# keyboard.net
KiCad netlist of a schematic drawn in EAGLE
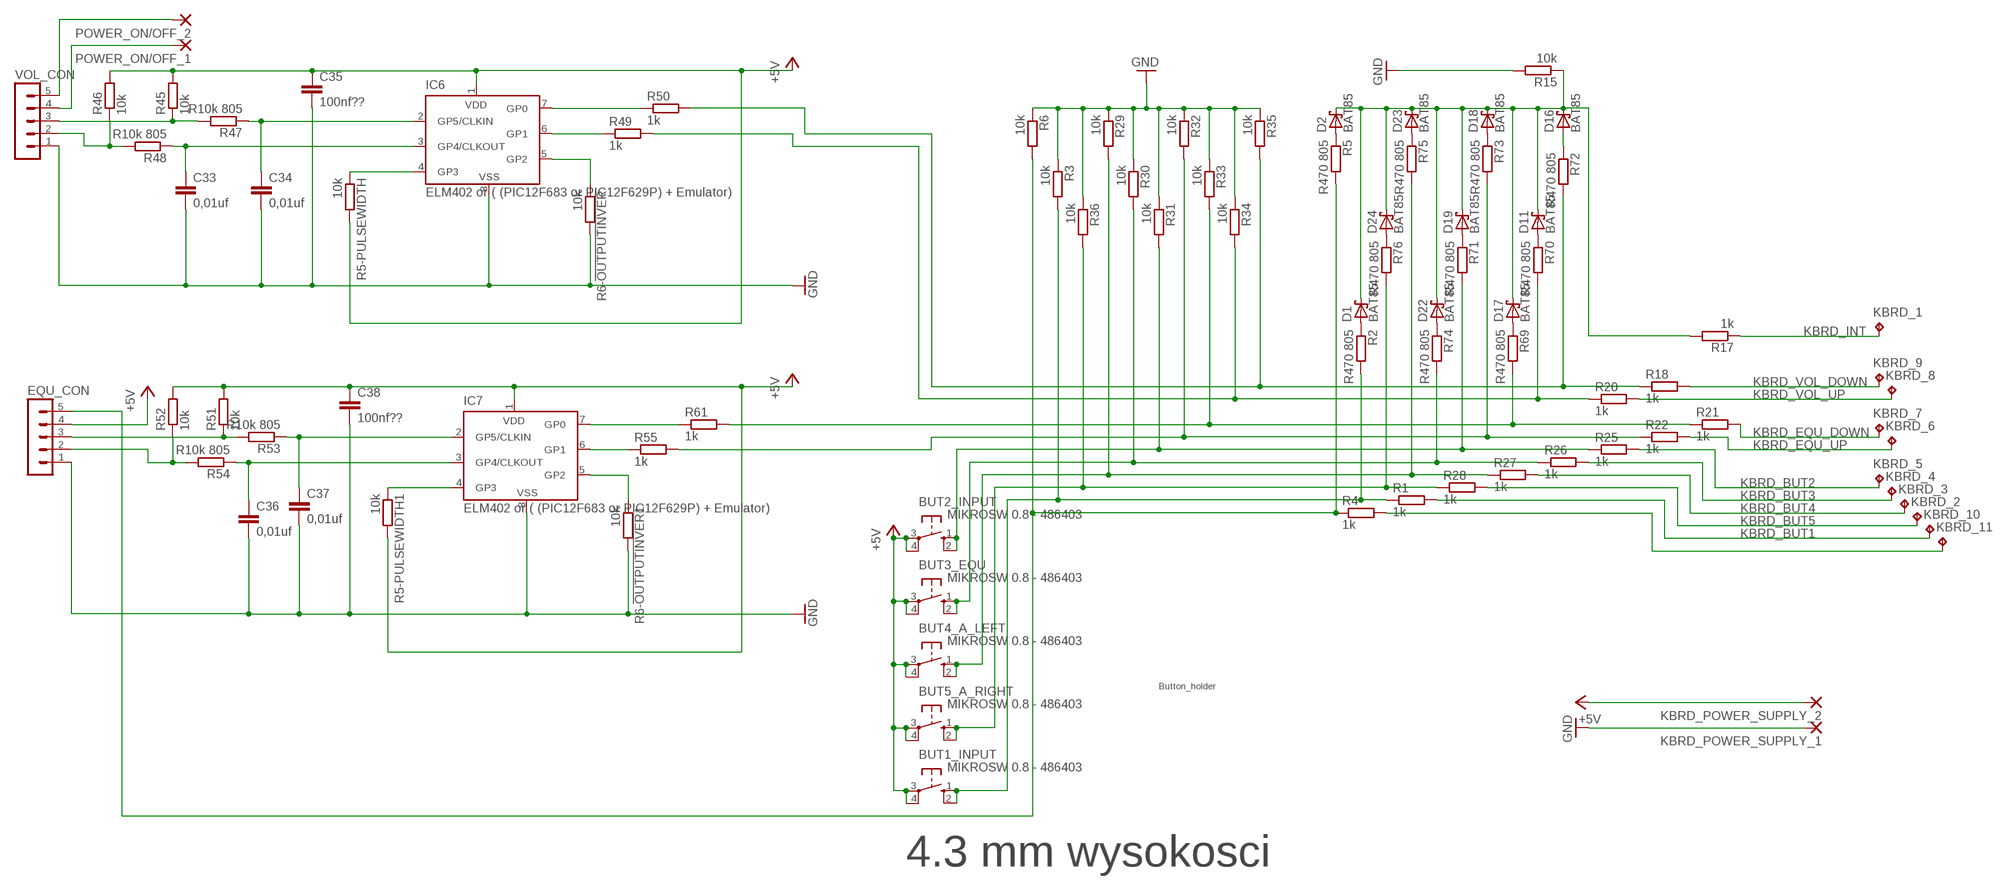
[diagram p0: schematic, sheet 1]

(export (version "E")
  (design (tool "Eeschema 10.0.6"))
  (components
    (comp (ref "BUT1_INPUT")
      (value "MIKROSW 0.8 - 486403")
      (footprint "eagle-import:B3F-10XX")
      (fields
        (field (name "MPN") "B3F-1000")
        (field (name "MF") "OMRON ELECTRONIC COMPONENTS")
        (field (name "MPN_1") "B3F-1000")
        (field (name "OC_FARNELL") "176432")
        (field (name "OC_NEWARK") "36M3542")
      )
      (libsource (lib "eagle-import") (part "10-XX"))
    )
    (comp (ref "BUT2_INPUT")
      (value "MIKROSW 0.8 - 486403")
      (footprint "eagle-import:B3F-10XX")
      (fields
        (field (name "MPN") "B3F-1000")
        (field (name "MF") "OMRON ELECTRONIC COMPONENTS")
        (field (name "MPN_1") "B3F-1000")
        (field (name "OC_FARNELL") "176432")
      )
      (libsource (lib "eagle-import") (part "10-XX"))
    )
    (comp (ref "BUT3_EQU")
      (value "MIKROSW 0.8 - 486403")
      (footprint "eagle-import:B3F-10XX")
      (fields
        (field (name "MPN") "B3F-1000")
        (field (name "MF") "OMRON ELECTRONIC COMPONENTS")
        (field (name "MPN_1") "B3F-1000")
        (field (name "OC_FARNELL") "176432")
      )
      (libsource (lib "eagle-import") (part "10-XX"))
    )
    (comp (ref "BUT4_A_LEFT")
      (value "MIKROSW 0.8 - 486403")
      (footprint "eagle-import:B3F-10XX")
      (fields
        (field (name "MPN") "B3F-1000")
        (field (name "MF") "OMRON ELECTRONIC COMPONENTS")
        (field (name "MPN_1") "B3F-1000")
        (field (name "OC_FARNELL") "176432")
      )
      (libsource (lib "eagle-import") (part "10-XX"))
    )
    (comp (ref "BUT5_A_RIGHT")
      (value "MIKROSW 0.8 - 486403")
      (footprint "eagle-import:B3F-10XX")
      (fields
        (field (name "MPN") "B3F-1000")
        (field (name "MF") "OMRON ELECTRONIC COMPONENTS")
        (field (name "MPN_1") "B3F-1000")
        (field (name "OC_FARNELL") "176432")
      )
      (libsource (lib "eagle-import") (part "10-XX"))
    )
    (comp (ref "C33")
      (value "0,01uf")
      (footprint "eagle-import:C0805")
      (libsource (lib "eagle-import") (part "C-EUC0805"))
    )
    (comp (ref "C34")
      (value "0,01uf")
      (footprint "eagle-import:C0805")
      (libsource (lib "eagle-import") (part "C-EUC0805"))
    )
    (comp (ref "C35")
      (value "100nf??")
      (footprint "eagle-import:C0805")
      (libsource (lib "eagle-import") (part "C-EUC0805"))
    )
    (comp (ref "C36")
      (value "0,01uf")
      (footprint "eagle-import:C0805")
      (libsource (lib "eagle-import") (part "C-EUC0805"))
    )
    (comp (ref "C37")
      (value "0,01uf")
      (footprint "eagle-import:C0805")
      (libsource (lib "eagle-import") (part "C-EUC0805"))
    )
    (comp (ref "C38")
      (value "100nf??")
      (footprint "eagle-import:C0805")
      (libsource (lib "eagle-import") (part "C-EUC0805"))
    )
    (comp (ref "D1")
      (value "BAT85")
      (footprint "eagle-import:DO34-5")
      (libsource (lib "eagle-import") (part "BAT85DO34-5"))
    )
    (comp (ref "D2")
      (value "BAT85")
      (footprint "eagle-import:DO34-5")
      (libsource (lib "eagle-import") (part "BAT85DO34-5"))
    )
    (comp (ref "D11")
      (value "BAT85")
      (footprint "eagle-import:DO34-5")
      (libsource (lib "eagle-import") (part "BAT85DO34-5"))
    )
    (comp (ref "D16")
      (value "BAT85")
      (footprint "eagle-import:DO34-5")
      (libsource (lib "eagle-import") (part "BAT85DO34-5"))
    )
    (comp (ref "D17")
      (value "BAT85")
      (footprint "eagle-import:DO34-5")
      (libsource (lib "eagle-import") (part "BAT85DO34-5"))
    )
    (comp (ref "D18")
      (value "BAT85")
      (footprint "eagle-import:DO34-5")
      (libsource (lib "eagle-import") (part "BAT85DO34-5"))
    )
    (comp (ref "D19")
      (value "BAT85")
      (footprint "eagle-import:DO34-5")
      (libsource (lib "eagle-import") (part "BAT85DO34-5"))
    )
    (comp (ref "D22")
      (value "BAT85")
      (footprint "eagle-import:DO34-5")
      (libsource (lib "eagle-import") (part "BAT85DO34-5"))
    )
    (comp (ref "D23")
      (value "BAT85")
      (footprint "eagle-import:DO34-5")
      (libsource (lib "eagle-import") (part "BAT85DO34-5"))
    )
    (comp (ref "D24")
      (value "BAT85")
      (footprint "eagle-import:DO34-5")
      (libsource (lib "eagle-import") (part "BAT85DO34-5"))
    )
    (comp (ref "EQU_CON")
      (value "MA05-1")
      (footprint "eagle-import:MA05-1")
      (fields (field (name "OC_FARNELL") "unknown") (field (name "OC_NEWARK") "unknown"))
      (libsource (lib "eagle-import") (part "MA05-1"))
    )
    (comp (ref "IC6")
      (value "ELM402 or ( (PIC12F683 or PIC12F629P) + Emulator)")
      (footprint "eagle-import:DIL8")
      (fields
        (field (name "MF") "MICROCHIP")
        (field (name "MPN") "PIC12F629-I/P")
        (field (name "MF_1") "MICROCHIP")
        (field (name "MPN_1") "PIC12F629-E/P")
        (field (name "OC_FARNELL") "1292253")
      )
      (libsource (lib "eagle-import") (part "PIC12F6P29"))
    )
    (comp (ref "IC7")
      (value "ELM402 or ( (PIC12F683 or PIC12F629P) + Emulator)")
      (footprint "eagle-import:DIL8")
      (fields
        (field (name "MF") "MICROCHIP")
        (field (name "MPN") "PIC12F629-I/P")
        (field (name "MF_1") "MICROCHIP")
        (field (name "MPN_1") "PIC12F629-E/P")
        (field (name "OC_FARNELL") "1292253")
      )
      (libsource (lib "eagle-import") (part "PIC12F6P29"))
    )
    (comp (ref "KBRD_1")
      (value "TPPAD1-13Y")
      (footprint "eagle-import:P1-13Y")
      (libsource (lib "eagle-import") (part "TPPAD1-13Y"))
    )
    (comp (ref "KBRD_2")
      (value "TPPAD1-13Y")
      (footprint "eagle-import:P1-13Y")
      (libsource (lib "eagle-import") (part "TPPAD1-13Y"))
    )
    (comp (ref "KBRD_3")
      (value "TPPAD1-13Y")
      (footprint "eagle-import:P1-13Y")
      (libsource (lib "eagle-import") (part "TPPAD1-13Y"))
    )
    (comp (ref "KBRD_4")
      (value "TPPAD1-13Y")
      (footprint "eagle-import:P1-13Y")
      (libsource (lib "eagle-import") (part "TPPAD1-13Y"))
    )
    (comp (ref "KBRD_5")
      (value "TPPAD1-13Y")
      (footprint "eagle-import:P1-13Y")
      (libsource (lib "eagle-import") (part "TPPAD1-13Y"))
    )
    (comp (ref "KBRD_6")
      (value "TPPAD1-13Y")
      (footprint "eagle-import:P1-13Y")
      (libsource (lib "eagle-import") (part "TPPAD1-13Y"))
    )
    (comp (ref "KBRD_7")
      (value "TPPAD1-13Y")
      (footprint "eagle-import:P1-13Y")
      (libsource (lib "eagle-import") (part "TPPAD1-13Y"))
    )
    (comp (ref "KBRD_8")
      (value "TPPAD1-13Y")
      (footprint "eagle-import:P1-13Y")
      (libsource (lib "eagle-import") (part "TPPAD1-13Y"))
    )
    (comp (ref "KBRD_9")
      (value "TPPAD1-13Y")
      (footprint "eagle-import:P1-13Y")
      (libsource (lib "eagle-import") (part "TPPAD1-13Y"))
    )
    (comp (ref "KBRD_10")
      (value "TPPAD1-13Y")
      (footprint "eagle-import:P1-13Y")
      (libsource (lib "eagle-import") (part "TPPAD1-13Y"))
    )
    (comp (ref "KBRD_11")
      (value "TPPAD1-13Y")
      (footprint "eagle-import:P1-13Y")
      (libsource (lib "eagle-import") (part "TPPAD1-13Y"))
    )
    (comp (ref "KBRD_POWER_SUPPLY_1")
      (value "1,6/0,9")
      (footprint "eagle-import:1,6_0,9")
      (libsource (lib "eagle-import") (part "1,6/0,9"))
    )
    (comp (ref "KBRD_POWER_SUPPLY_2")
      (value "1,6/0,9")
      (footprint "eagle-import:1,6_0,9")
      (libsource (lib "eagle-import") (part "1,6/0,9"))
    )
    (comp (ref "POWER_ON/OFF_1")
      (value "2,15/1,0")
      (footprint "eagle-import:2,15_1,0")
      (libsource (lib "eagle-import") (part "2,15/1,0"))
    )
    (comp (ref "POWER_ON/OFF_2")
      (value "2,15/1,0")
      (footprint "eagle-import:2,15_1,0")
      (libsource (lib "eagle-import") (part "2,15/1,0"))
    )
    (comp (ref "R1")
      (value "1k")
      (footprint "eagle-import:R0805")
      (libsource (lib "eagle-import") (part "R-EU_R0805"))
    )
    (comp (ref "R2")
      (value "R470 805")
      (footprint "eagle-import:R0805")
      (libsource (lib "eagle-import") (part "R-EU_R0805"))
    )
    (comp (ref "R3")
      (value "10k")
      (footprint "eagle-import:R0805")
      (libsource (lib "eagle-import") (part "R-EU_R0805"))
    )
    (comp (ref "R4")
      (value "1k")
      (footprint "eagle-import:R0805")
      (libsource (lib "eagle-import") (part "R-EU_R0805"))
    )
    (comp (ref "R5")
      (value "R470 805")
      (footprint "eagle-import:R0805")
      (libsource (lib "eagle-import") (part "R-EU_R0805"))
    )
    (comp (ref "R5-PULSEWIDTH")
      (value "10k")
      (footprint "eagle-import:0204_7")
      (libsource (lib "eagle-import") (part "resistor_R-EU_0204/7"))
    )
    (comp (ref "R5-PULSEWIDTH1")
      (value "10k")
      (footprint "eagle-import:0204_7")
      (libsource (lib "eagle-import") (part "resistor_R-EU_0204/7"))
    )
    (comp (ref "R6")
      (value "10k")
      (footprint "eagle-import:0204_5")
      (libsource (lib "eagle-import") (part "R-EU_0204/5"))
    )
    (comp (ref "R6-!OUTPUTINVER!")
      (value "10k")
      (footprint "eagle-import:R0805")
      (libsource (lib "eagle-import") (part "resistor_R-EU_R0805"))
    )
    (comp (ref "R6-!OUTPUTINVER!1")
      (value "10k")
      (footprint "eagle-import:R0805")
      (libsource (lib "eagle-import") (part "resistor_R-EU_R0805"))
    )
    (comp (ref "R15")
      (value "10k")
      (footprint "eagle-import:R0805")
      (libsource (lib "eagle-import") (part "R-EU_R0805"))
    )
    (comp (ref "R17")
      (value "1k")
      (footprint "eagle-import:R0805")
      (libsource (lib "eagle-import") (part "R-EU_R0805"))
    )
    (comp (ref "R18")
      (value "1k")
      (footprint "eagle-import:R0805")
      (libsource (lib "eagle-import") (part "R-EU_R0805"))
    )
    (comp (ref "R20")
      (value "1k")
      (footprint "eagle-import:R0805")
      (libsource (lib "eagle-import") (part "R-EU_R0805"))
    )
    (comp (ref "R21")
      (value "1k")
      (footprint "eagle-import:R0805")
      (libsource (lib "eagle-import") (part "R-EU_R0805"))
    )
    (comp (ref "R22")
      (value "1k")
      (footprint "eagle-import:R0805")
      (libsource (lib "eagle-import") (part "R-EU_R0805"))
    )
    (comp (ref "R25")
      (value "1k")
      (footprint "eagle-import:R0805")
      (libsource (lib "eagle-import") (part "R-EU_R0805"))
    )
    (comp (ref "R26")
      (value "1k")
      (footprint "eagle-import:R0805")
      (libsource (lib "eagle-import") (part "R-EU_R0805"))
    )
    (comp (ref "R27")
      (value "1k")
      (footprint "eagle-import:R0805")
      (libsource (lib "eagle-import") (part "R-EU_R0805"))
    )
    (comp (ref "R28")
      (value "1k")
      (footprint "eagle-import:R0805")
      (libsource (lib "eagle-import") (part "R-EU_R0805"))
    )
    (comp (ref "R29")
      (value "10k")
      (footprint "eagle-import:R0805")
      (libsource (lib "eagle-import") (part "R-EU_R0805"))
    )
    (comp (ref "R30")
      (value "10k")
      (footprint "eagle-import:R0805")
      (libsource (lib "eagle-import") (part "R-EU_R0805"))
    )
    (comp (ref "R31")
      (value "10k")
      (footprint "eagle-import:M0805")
      (libsource (lib "eagle-import") (part "R-EU_M0805"))
    )
    (comp (ref "R32")
      (value "10k")
      (footprint "eagle-import:0204_5")
      (libsource (lib "eagle-import") (part "R-EU_0204/5"))
    )
    (comp (ref "R33")
      (value "10k")
      (footprint "eagle-import:0204_5")
      (libsource (lib "eagle-import") (part "R-EU_0204/5"))
    )
    (comp (ref "R34")
      (value "10k")
      (footprint "eagle-import:0204_5")
      (libsource (lib "eagle-import") (part "R-EU_0204/5"))
    )
    (comp (ref "R35")
      (value "10k")
      (footprint "eagle-import:0204_5")
      (libsource (lib "eagle-import") (part "R-EU_0204/5"))
    )
    (comp (ref "R36")
      (value "10k")
      (footprint "eagle-import:R0805")
      (libsource (lib "eagle-import") (part "R-EU_R0805"))
    )
    (comp (ref "R45")
      (value "10k")
      (footprint "eagle-import:R0805")
      (libsource (lib "eagle-import") (part "resistor_R-EU_R0805"))
    )
    (comp (ref "R46")
      (value "10k")
      (footprint "eagle-import:R0805")
      (libsource (lib "eagle-import") (part "resistor_R-EU_R0805"))
    )
    (comp (ref "R47")
      (value "R10k 805")
      (footprint "eagle-import:R0805")
      (libsource (lib "eagle-import") (part "resistor_R-EU_R0805"))
    )
    (comp (ref "R48")
      (value "R10k 805")
      (footprint "eagle-import:R0805")
      (libsource (lib "eagle-import") (part "resistor_R-EU_R0805"))
    )
    (comp (ref "R49")
      (value "1k")
      (footprint "eagle-import:R0805")
      (libsource (lib "eagle-import") (part "resistor_R-EU_R0805"))
    )
    (comp (ref "R50")
      (value "1k")
      (footprint "eagle-import:R0805")
      (libsource (lib "eagle-import") (part "resistor_R-EU_R0805"))
    )
    (comp (ref "R51")
      (value "10k")
      (footprint "eagle-import:M0805")
      (libsource (lib "eagle-import") (part "resistor_R-EU_M0805"))
    )
    (comp (ref "R52")
      (value "10k")
      (footprint "eagle-import:M0805")
      (libsource (lib "eagle-import") (part "resistor_R-EU_M0805"))
    )
    (comp (ref "R53")
      (value "R10k 805")
      (footprint "eagle-import:R0805")
      (libsource (lib "eagle-import") (part "resistor_R-EU_R0805"))
    )
    (comp (ref "R54")
      (value "R10k 805")
      (footprint "eagle-import:R0805")
      (libsource (lib "eagle-import") (part "resistor_R-EU_R0805"))
    )
    (comp (ref "R55")
      (value "1k")
      (footprint "eagle-import:R0805")
      (libsource (lib "eagle-import") (part "resistor_R-EU_R0805"))
    )
    (comp (ref "R61")
      (value "1k")
      (footprint "eagle-import:R0805")
      (libsource (lib "eagle-import") (part "resistor_R-EU_R0805"))
    )
    (comp (ref "R69")
      (value "R470 805")
      (footprint "eagle-import:R0805")
      (libsource (lib "eagle-import") (part "R-EU_R0805"))
    )
    (comp (ref "R70")
      (value "R470 805")
      (footprint "eagle-import:R0805")
      (libsource (lib "eagle-import") (part "R-EU_R0805"))
    )
    (comp (ref "R71")
      (value "R470 805")
      (footprint "eagle-import:R0805")
      (libsource (lib "eagle-import") (part "R-EU_R0805"))
    )
    (comp (ref "R72")
      (value "R470 805")
      (footprint "eagle-import:R0805")
      (libsource (lib "eagle-import") (part "R-EU_R0805"))
    )
    (comp (ref "R73")
      (value "R470 805")
      (footprint "eagle-import:R0805")
      (libsource (lib "eagle-import") (part "R-EU_R0805"))
    )
    (comp (ref "R74")
      (value "R470 805")
      (footprint "eagle-import:R0805")
      (libsource (lib "eagle-import") (part "R-EU_R0805"))
    )
    (comp (ref "R75")
      (value "R470 805")
      (footprint "eagle-import:R0805")
      (libsource (lib "eagle-import") (part "R-EU_R0805"))
    )
    (comp (ref "R76")
      (value "R470 805")
      (footprint "eagle-import:R0805")
      (libsource (lib "eagle-import") (part "R-EU_R0805"))
    )
    (comp (ref "U$1")
      (value "TRZYMADLO")
      (footprint "eagle-import:TRZYMADLO_POPYCHACZY")
      (libsource (lib "eagle-import") (part "TRZYMADLO"))
    )
    (comp (ref "VOL_CON")
      (value "MA05-1")
      (footprint "eagle-import:MA05-1")
      (libsource (lib "eagle-import") (part "MA05-1"))
    )
  )
  (nets
    (net (code "1") (name "+5V") (class "Default")
      (node (ref "BUT1_INPUT") (pin "3") (pinfunction "P_3") (pintype "passive"))
      (node (ref "BUT1_INPUT") (pin "4") (pinfunction "P1_4") (pintype "passive"))
      (node (ref "BUT2_INPUT") (pin "3") (pinfunction "P_3") (pintype "passive"))
      (node (ref "BUT2_INPUT") (pin "4") (pinfunction "P1_4") (pintype "passive"))
      (node (ref "BUT3_EQU") (pin "3") (pinfunction "P_3") (pintype "passive"))
      (node (ref "BUT3_EQU") (pin "4") (pinfunction "P1_4") (pintype "passive"))
      (node (ref "BUT4_A_LEFT") (pin "3") (pinfunction "P_3") (pintype "passive"))
      (node (ref "BUT4_A_LEFT") (pin "4") (pinfunction "P1_4") (pintype "passive"))
      (node (ref "BUT5_A_RIGHT") (pin "3") (pinfunction "P_3") (pintype "passive"))
      (node (ref "BUT5_A_RIGHT") (pin "4") (pinfunction "P1_4") (pintype "passive"))
      (node (ref "C35") (pin "1") (pinfunction "1_1") (pintype "passive"))
      (node (ref "C38") (pin "1") (pinfunction "1_1") (pintype "passive"))
      (node (ref "EQU_CON") (pin "4") (pinfunction "4_4") (pintype "passive"))
      (node (ref "IC6") (pin "1") (pinfunction "VDD_1") (pintype "power_in"))
      (node (ref "IC7") (pin "1") (pinfunction "VDD_1") (pintype "power_in"))
      (node (ref "KBRD_POWER_SUPPLY_2") (pin "1") (pinfunction "P_1") (pintype "passive"))
      (node (ref "R45") (pin "2") (pinfunction "2_2") (pintype "passive"))
      (node (ref "R46") (pin "2") (pinfunction "2_2") (pintype "passive"))
      (node (ref "R5-PULSEWIDTH") (pin "2") (pinfunction "2_2") (pintype "passive"))
      (node (ref "R5-PULSEWIDTH1") (pin "2") (pinfunction "2_2") (pintype "passive"))
      (node (ref "R51") (pin "2") (pinfunction "2_2") (pintype "passive"))
      (node (ref "R52") (pin "2") (pinfunction "2_2") (pintype "passive"))
    )
    (net (code "2") (name "/KBRD_BUT1") (class "Default")
      (node (ref "KBRD_10") (pin "TP") (pinfunction "TP_TP") (pintype "input"))
      (node (ref "R1") (pin "2") (pinfunction "2_2") (pintype "passive"))
    )
    (net (code "3") (name "/KBRD_BUT2") (class "Default")
      (node (ref "KBRD_5") (pin "TP") (pinfunction "TP_TP") (pintype "input"))
      (node (ref "R25") (pin "2") (pinfunction "2_2") (pintype "passive"))
    )
    (net (code "4") (name "/KBRD_BUT3") (class "Default")
      (node (ref "KBRD_4") (pin "TP") (pinfunction "TP_TP") (pintype "input"))
      (node (ref "R26") (pin "2") (pinfunction "2_2") (pintype "passive"))
    )
    (net (code "5") (name "/KBRD_BUT4") (class "Default")
      (node (ref "KBRD_3") (pin "TP") (pinfunction "TP_TP") (pintype "input"))
      (node (ref "R27") (pin "2") (pinfunction "2_2") (pintype "passive"))
    )
    (net (code "6") (name "/KBRD_BUT5") (class "Default")
      (node (ref "KBRD_2") (pin "TP") (pinfunction "TP_TP") (pintype "input"))
      (node (ref "R28") (pin "2") (pinfunction "2_2") (pintype "passive"))
    )
    (net (code "7") (name "/KBRD_EQU_DOWN") (class "Default")
      (node (ref "KBRD_7") (pin "TP") (pinfunction "TP_TP") (pintype "input"))
      (node (ref "R21") (pin "2") (pinfunction "2_2") (pintype "passive"))
    )
    (net (code "8") (name "/KBRD_EQU_UP") (class "Default")
      (node (ref "KBRD_6") (pin "TP") (pinfunction "TP_TP") (pintype "input"))
      (node (ref "R22") (pin "2") (pinfunction "2_2") (pintype "passive"))
    )
    (net (code "9") (name "/KBRD_INT") (class "Default")
      (node (ref "KBRD_1") (pin "TP") (pinfunction "TP_TP") (pintype "input"))
      (node (ref "R17") (pin "1") (pinfunction "1_1") (pintype "passive"))
    )
    (net (code "10") (name "/KBRD_VOL_DOWN") (class "Default")
      (node (ref "KBRD_9") (pin "TP") (pinfunction "TP_TP") (pintype "input"))
      (node (ref "R18") (pin "2") (pinfunction "2_2") (pintype "passive"))
    )
    (net (code "11") (name "/KBRD_VOL_UP") (class "Default")
      (node (ref "KBRD_8") (pin "TP") (pinfunction "TP_TP") (pintype "input"))
      (node (ref "R20") (pin "2") (pinfunction "2_2") (pintype "passive"))
    )
    (net (code "12") (name "GND") (class "Default")
      (node (ref "C33") (pin "2") (pinfunction "2_2") (pintype "passive"))
      (node (ref "C34") (pin "2") (pinfunction "2_2") (pintype "passive"))
      (node (ref "C35") (pin "2") (pinfunction "2_2") (pintype "passive"))
      (node (ref "C36") (pin "2") (pinfunction "2_2") (pintype "passive"))
      (node (ref "C37") (pin "2") (pinfunction "2_2") (pintype "passive"))
      (node (ref "C38") (pin "2") (pinfunction "2_2") (pintype "passive"))
      (node (ref "EQU_CON") (pin "1") (pinfunction "1_1") (pintype "passive"))
      (node (ref "IC6") (pin "8") (pinfunction "VSS_8") (pintype "power_in"))
      (node (ref "IC7") (pin "8") (pinfunction "VSS_8") (pintype "power_in"))
      (node (ref "KBRD_POWER_SUPPLY_1") (pin "1") (pinfunction "P_1") (pintype "passive"))
      (node (ref "R15") (pin "2") (pinfunction "2_2") (pintype "passive"))
      (node (ref "R29") (pin "1") (pinfunction "1_1") (pintype "passive"))
      (node (ref "R3") (pin "1") (pinfunction "1_1") (pintype "passive"))
      (node (ref "R30") (pin "1") (pinfunction "1_1") (pintype "passive"))
      (node (ref "R31") (pin "1") (pinfunction "1_1") (pintype "passive"))
      (node (ref "R32") (pin "1") (pinfunction "1_1") (pintype "passive"))
      (node (ref "R33") (pin "1") (pinfunction "1_1") (pintype "passive"))
      (node (ref "R34") (pin "1") (pinfunction "1_1") (pintype "passive"))
      (node (ref "R35") (pin "1") (pinfunction "1_1") (pintype "passive"))
      (node (ref "R36") (pin "1") (pinfunction "1_1") (pintype "passive"))
      (node (ref "R6") (pin "1") (pinfunction "1_1") (pintype "passive"))
      (node (ref "R6-!OUTPUTINVER!") (pin "2") (pinfunction "2_2") (pintype "passive"))
      (node (ref "R6-!OUTPUTINVER!1") (pin "2") (pinfunction "2_2") (pintype "passive"))
      (node (ref "VOL_CON") (pin "1") (pinfunction "1_1") (pintype "passive"))
    )
    (net (code "13") (name "Net-(BUT1_INPUT-S)") (class "Default")
      (node (ref "BUT1_INPUT") (pin "1") (pinfunction "S_1") (pintype "passive"))
      (node (ref "BUT1_INPUT") (pin "2") (pinfunction "S1_2") (pintype "passive"))
      (node (ref "R1") (pin "1") (pinfunction "1_1") (pintype "passive"))
      (node (ref "R2") (pin "2") (pinfunction "2_2") (pintype "passive"))
      (node (ref "R3") (pin "2") (pinfunction "2_2") (pintype "passive"))
    )
    (net (code "14") (name "Net-(BUT2_INPUT-S)") (class "Default")
      (node (ref "BUT2_INPUT") (pin "1") (pinfunction "S_1") (pintype "passive"))
      (node (ref "BUT2_INPUT") (pin "2") (pinfunction "S1_2") (pintype "passive"))
      (node (ref "R25") (pin "1") (pinfunction "1_1") (pintype "passive"))
      (node (ref "R31") (pin "2") (pinfunction "2_2") (pintype "passive"))
      (node (ref "R71") (pin "2") (pinfunction "2_2") (pintype "passive"))
    )
    (net (code "15") (name "Net-(BUT3_EQU-S)") (class "Default")
      (node (ref "BUT3_EQU") (pin "1") (pinfunction "S_1") (pintype "passive"))
      (node (ref "BUT3_EQU") (pin "2") (pinfunction "S1_2") (pintype "passive"))
      (node (ref "R26") (pin "1") (pinfunction "1_1") (pintype "passive"))
      (node (ref "R30") (pin "2") (pinfunction "2_2") (pintype "passive"))
      (node (ref "R74") (pin "2") (pinfunction "2_2") (pintype "passive"))
    )
    (net (code "16") (name "Net-(BUT4_A_LEFT-S)") (class "Default")
      (node (ref "BUT4_A_LEFT") (pin "1") (pinfunction "S_1") (pintype "passive"))
      (node (ref "BUT4_A_LEFT") (pin "2") (pinfunction "S1_2") (pintype "passive"))
      (node (ref "R27") (pin "1") (pinfunction "1_1") (pintype "passive"))
      (node (ref "R29") (pin "2") (pinfunction "2_2") (pintype "passive"))
      (node (ref "R75") (pin "2") (pinfunction "2_2") (pintype "passive"))
    )
    (net (code "17") (name "Net-(BUT5_A_RIGHT-S)") (class "Default")
      (node (ref "BUT5_A_RIGHT") (pin "1") (pinfunction "S_1") (pintype "passive"))
      (node (ref "BUT5_A_RIGHT") (pin "2") (pinfunction "S1_2") (pintype "passive"))
      (node (ref "R28") (pin "1") (pinfunction "1_1") (pintype "passive"))
      (node (ref "R36") (pin "2") (pinfunction "2_2") (pintype "passive"))
      (node (ref "R76") (pin "2") (pinfunction "2_2") (pintype "passive"))
    )
    (net (code "18") (name "Net-(D1-PadA)") (class "Default")
      (node (ref "D1") (pin "A") (pinfunction "A_A") (pintype "passive"))
      (node (ref "R2") (pin "1") (pinfunction "1_1") (pintype "passive"))
    )
    (net (code "19") (name "Net-(D1-PadC)") (class "Default")
      (node (ref "D1") (pin "C") (pinfunction "C_C") (pintype "passive"))
      (node (ref "D11") (pin "C") (pinfunction "C_C") (pintype "passive"))
      (node (ref "D16") (pin "C") (pinfunction "C_C") (pintype "passive"))
      (node (ref "D17") (pin "C") (pinfunction "C_C") (pintype "passive"))
      (node (ref "D18") (pin "C") (pinfunction "C_C") (pintype "passive"))
      (node (ref "D19") (pin "C") (pinfunction "C_C") (pintype "passive"))
      (node (ref "D2") (pin "C") (pinfunction "C_C") (pintype "passive"))
      (node (ref "D22") (pin "C") (pinfunction "C_C") (pintype "passive"))
      (node (ref "D23") (pin "C") (pinfunction "C_C") (pintype "passive"))
      (node (ref "D24") (pin "C") (pinfunction "C_C") (pintype "passive"))
      (node (ref "R15") (pin "1") (pinfunction "1_1") (pintype "passive"))
      (node (ref "R17") (pin "2") (pinfunction "2_2") (pintype "passive"))
    )
    (net (code "20") (name "Net-(D2-PadA)") (class "Default")
      (node (ref "D2") (pin "A") (pinfunction "A_A") (pintype "passive"))
      (node (ref "R5") (pin "1") (pinfunction "1_1") (pintype "passive"))
    )
    (net (code "21") (name "Net-(D11-PadA)") (class "Default")
      (node (ref "D11") (pin "A") (pinfunction "A_A") (pintype "passive"))
      (node (ref "R70") (pin "1") (pinfunction "1_1") (pintype "passive"))
    )
    (net (code "22") (name "Net-(D16-PadA)") (class "Default")
      (node (ref "D16") (pin "A") (pinfunction "A_A") (pintype "passive"))
      (node (ref "R72") (pin "1") (pinfunction "1_1") (pintype "passive"))
    )
    (net (code "23") (name "Net-(D17-PadA)") (class "Default")
      (node (ref "D17") (pin "A") (pinfunction "A_A") (pintype "passive"))
      (node (ref "R69") (pin "1") (pinfunction "1_1") (pintype "passive"))
    )
    (net (code "24") (name "Net-(D18-PadA)") (class "Default")
      (node (ref "D18") (pin "A") (pinfunction "A_A") (pintype "passive"))
      (node (ref "R73") (pin "1") (pinfunction "1_1") (pintype "passive"))
    )
    (net (code "25") (name "Net-(D19-PadA)") (class "Default")
      (node (ref "D19") (pin "A") (pinfunction "A_A") (pintype "passive"))
      (node (ref "R71") (pin "1") (pinfunction "1_1") (pintype "passive"))
    )
    (net (code "26") (name "Net-(D22-PadA)") (class "Default")
      (node (ref "D22") (pin "A") (pinfunction "A_A") (pintype "passive"))
      (node (ref "R74") (pin "1") (pinfunction "1_1") (pintype "passive"))
    )
    (net (code "27") (name "Net-(D23-PadA)") (class "Default")
      (node (ref "D23") (pin "A") (pinfunction "A_A") (pintype "passive"))
      (node (ref "R75") (pin "1") (pinfunction "1_1") (pintype "passive"))
    )
    (net (code "28") (name "Net-(D24-PadA)") (class "Default")
      (node (ref "D24") (pin "A") (pinfunction "A_A") (pintype "passive"))
      (node (ref "R76") (pin "1") (pinfunction "1_1") (pintype "passive"))
    )
    (net (code "29") (name "Net-(EQU_CON-Pad2)") (class "Default")
      (node (ref "EQU_CON") (pin "2") (pinfunction "2_2") (pintype "passive"))
      (node (ref "R52") (pin "1") (pinfunction "1_1") (pintype "passive"))
      (node (ref "R54") (pin "2") (pinfunction "2_2") (pintype "passive"))
    )
    (net (code "30") (name "Net-(EQU_CON-Pad3)") (class "Default")
      (node (ref "EQU_CON") (pin "3") (pinfunction "3_3") (pintype "passive"))
      (node (ref "R51") (pin "1") (pinfunction "1_1") (pintype "passive"))
      (node (ref "R53") (pin "2") (pinfunction "2_2") (pintype "passive"))
    )
    (net (code "31") (name "Net-(EQU_CON-Pad5)") (class "Default")
      (node (ref "EQU_CON") (pin "5") (pinfunction "5_5") (pintype "passive"))
      (node (ref "R4") (pin "1") (pinfunction "1_1") (pintype "passive"))
      (node (ref "R5") (pin "2") (pinfunction "2_2") (pintype "passive"))
      (node (ref "R6") (pin "2") (pinfunction "2_2") (pintype "passive"))
    )
    (net (code "32") (name "Net-(IC6-GP0)") (class "Default")
      (node (ref "IC6") (pin "7") (pinfunction "GP0_7") (pintype "bidirectional"))
      (node (ref "R50") (pin "1") (pinfunction "1_1") (pintype "passive"))
    )
    (net (code "33") (name "Net-(IC6-GP1)") (class "Default")
      (node (ref "IC6") (pin "6") (pinfunction "GP1_6") (pintype "bidirectional"))
      (node (ref "R49") (pin "1") (pinfunction "1_1") (pintype "passive"))
    )
    (net (code "34") (name "Net-(IC6-GP2)") (class "Default")
      (node (ref "IC6") (pin "5") (pinfunction "GP2_5") (pintype "bidirectional"))
      (node (ref "R6-!OUTPUTINVER!") (pin "1") (pinfunction "1_1") (pintype "passive"))
    )
    (net (code "35") (name "Net-(IC6-GP3)") (class "Default")
      (node (ref "IC6") (pin "4") (pinfunction "GP3_4") (pintype "input"))
      (node (ref "R5-PULSEWIDTH") (pin "1") (pinfunction "1_1") (pintype "passive"))
    )
    (net (code "36") (name "Net-(IC6-GP4{slash}CLKOUT)") (class "Default")
      (node (ref "C33") (pin "1") (pinfunction "1_1") (pintype "passive"))
      (node (ref "IC6") (pin "3") (pinfunction "GP4/CLKOUT_3") (pintype "bidirectional"))
      (node (ref "R48") (pin "1") (pinfunction "1_1") (pintype "passive"))
    )
    (net (code "37") (name "Net-(IC6-GP5{slash}CLKIN)") (class "Default")
      (node (ref "C34") (pin "1") (pinfunction "1_1") (pintype "passive"))
      (node (ref "IC6") (pin "2") (pinfunction "GP5/CLKIN_2") (pintype "bidirectional"))
      (node (ref "R47") (pin "1") (pinfunction "1_1") (pintype "passive"))
    )
    (net (code "38") (name "Net-(IC7-GP0)") (class "Default")
      (node (ref "IC7") (pin "7") (pinfunction "GP0_7") (pintype "bidirectional"))
      (node (ref "R61") (pin "1") (pinfunction "1_1") (pintype "passive"))
    )
    (net (code "39") (name "Net-(IC7-GP1)") (class "Default")
      (node (ref "IC7") (pin "6") (pinfunction "GP1_6") (pintype "bidirectional"))
      (node (ref "R55") (pin "1") (pinfunction "1_1") (pintype "passive"))
    )
    (net (code "40") (name "Net-(IC7-GP2)") (class "Default")
      (node (ref "IC7") (pin "5") (pinfunction "GP2_5") (pintype "bidirectional"))
      (node (ref "R6-!OUTPUTINVER!1") (pin "1") (pinfunction "1_1") (pintype "passive"))
    )
    (net (code "41") (name "Net-(IC7-GP3)") (class "Default")
      (node (ref "IC7") (pin "4") (pinfunction "GP3_4") (pintype "input"))
      (node (ref "R5-PULSEWIDTH1") (pin "1") (pinfunction "1_1") (pintype "passive"))
    )
    (net (code "42") (name "Net-(IC7-GP4{slash}CLKOUT)") (class "Default")
      (node (ref "C36") (pin "1") (pinfunction "1_1") (pintype "passive"))
      (node (ref "IC7") (pin "3") (pinfunction "GP4/CLKOUT_3") (pintype "bidirectional"))
      (node (ref "R54") (pin "1") (pinfunction "1_1") (pintype "passive"))
    )
    (net (code "43") (name "Net-(IC7-GP5{slash}CLKIN)") (class "Default")
      (node (ref "C37") (pin "1") (pinfunction "1_1") (pintype "passive"))
      (node (ref "IC7") (pin "2") (pinfunction "GP5/CLKIN_2") (pintype "bidirectional"))
      (node (ref "R53") (pin "1") (pinfunction "1_1") (pintype "passive"))
    )
    (net (code "44") (name "Net-(KBRD_11-PadTP)") (class "Default")
      (node (ref "KBRD_11") (pin "TP") (pinfunction "TP_TP") (pintype "input"))
      (node (ref "R4") (pin "2") (pinfunction "2_2") (pintype "passive"))
    )
    (net (code "45") (name "Net-(POWER_ON/OFF_1-P)") (class "Default")
      (node (ref "POWER_ON/OFF_1") (pin "1") (pinfunction "P_1") (pintype "passive"))
      (node (ref "VOL_CON") (pin "4") (pinfunction "4_4") (pintype "passive"))
    )
    (net (code "46") (name "Net-(POWER_ON/OFF_2-P)") (class "Default")
      (node (ref "POWER_ON/OFF_2") (pin "1") (pinfunction "P_1") (pintype "passive"))
      (node (ref "VOL_CON") (pin "5") (pinfunction "5_5") (pintype "passive"))
    )
    (net (code "47") (name "Net-(R18-Pad1)") (class "Default")
      (node (ref "R18") (pin "1") (pinfunction "1_1") (pintype "passive"))
      (node (ref "R35") (pin "2") (pinfunction "2_2") (pintype "passive"))
      (node (ref "R50") (pin "2") (pinfunction "2_2") (pintype "passive"))
      (node (ref "R72") (pin "2") (pinfunction "2_2") (pintype "passive"))
    )
    (net (code "48") (name "Net-(R20-Pad1)") (class "Default")
      (node (ref "R20") (pin "1") (pinfunction "1_1") (pintype "passive"))
      (node (ref "R34") (pin "2") (pinfunction "2_2") (pintype "passive"))
      (node (ref "R49") (pin "2") (pinfunction "2_2") (pintype "passive"))
      (node (ref "R70") (pin "2") (pinfunction "2_2") (pintype "passive"))
    )
    (net (code "49") (name "Net-(R21-Pad1)") (class "Default")
      (node (ref "R21") (pin "1") (pinfunction "1_1") (pintype "passive"))
      (node (ref "R33") (pin "2") (pinfunction "2_2") (pintype "passive"))
      (node (ref "R61") (pin "2") (pinfunction "2_2") (pintype "passive"))
      (node (ref "R69") (pin "2") (pinfunction "2_2") (pintype "passive"))
    )
    (net (code "50") (name "Net-(R22-Pad1)") (class "Default")
      (node (ref "R22") (pin "1") (pinfunction "1_1") (pintype "passive"))
      (node (ref "R32") (pin "2") (pinfunction "2_2") (pintype "passive"))
      (node (ref "R55") (pin "2") (pinfunction "2_2") (pintype "passive"))
      (node (ref "R73") (pin "2") (pinfunction "2_2") (pintype "passive"))
    )
    (net (code "51") (name "Net-(R45-Pad1)") (class "Default")
      (node (ref "R45") (pin "1") (pinfunction "1_1") (pintype "passive"))
      (node (ref "R47") (pin "2") (pinfunction "2_2") (pintype "passive"))
      (node (ref "VOL_CON") (pin "3") (pinfunction "3_3") (pintype "passive"))
    )
    (net (code "52") (name "Net-(R46-Pad1)") (class "Default")
      (node (ref "R46") (pin "1") (pinfunction "1_1") (pintype "passive"))
      (node (ref "R48") (pin "2") (pinfunction "2_2") (pintype "passive"))
      (node (ref "VOL_CON") (pin "2") (pinfunction "2_2") (pintype "passive"))
    )
  )
)
